# gat8_rev_1.net
KiCad netlist of a schematic drawn in EAGLE
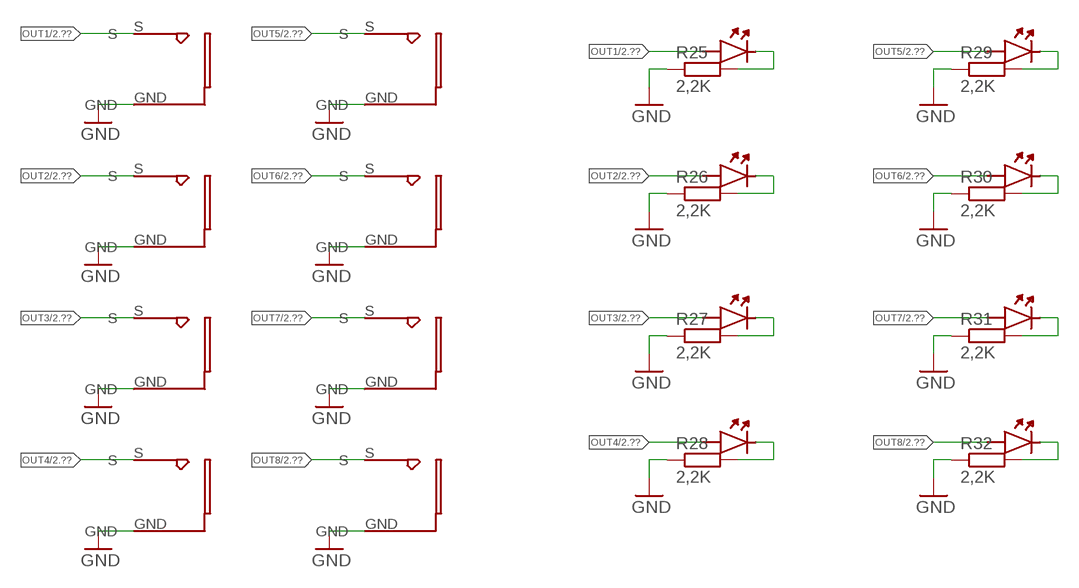
[diagram p0: schematic, sheet 1]
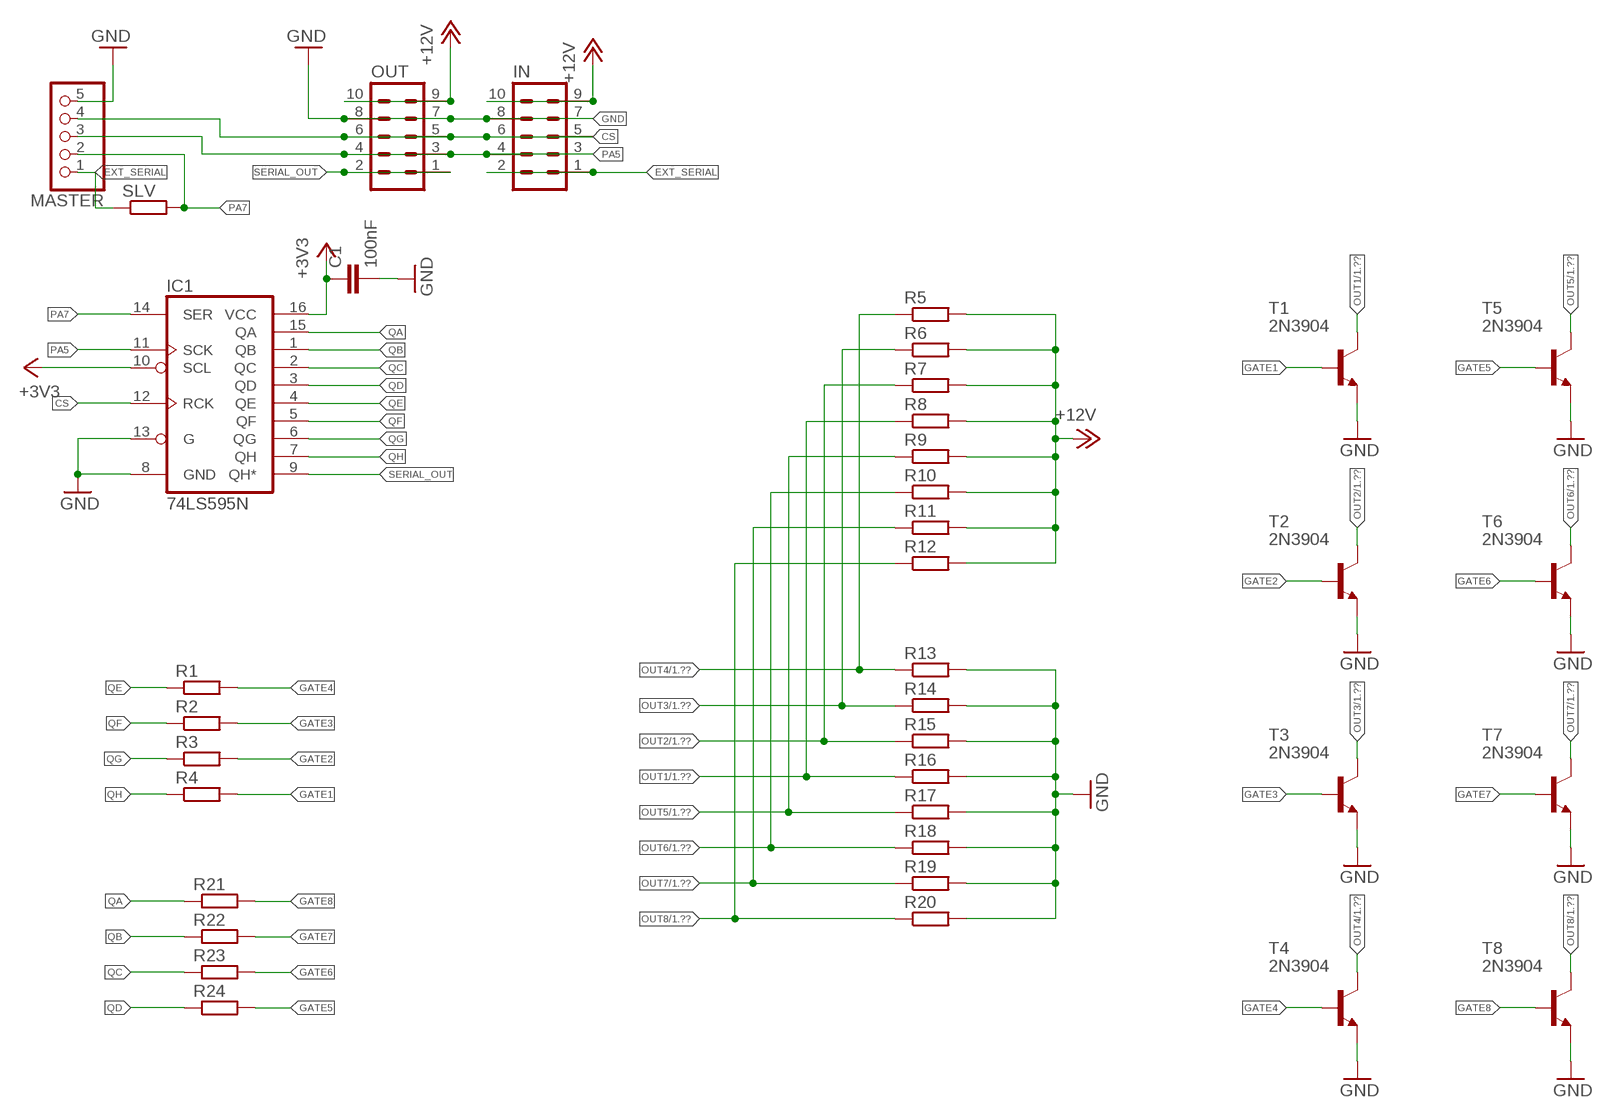
[diagram p1: schematic, sheet 2]
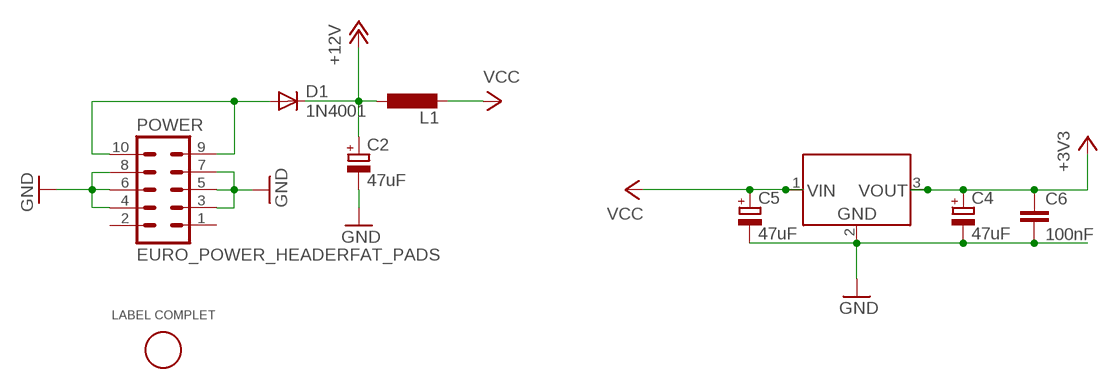
[diagram p2: schematic, sheet 3]

(export (version "E")
  (design (tool "Eeschema 10.0.6"))
  (components
    (comp (ref "C2")
      (value "47uF")
      (footprint "eagle-import:E2-5")
      (libsource (lib "eagle-import") (part "CPOL-EUE2-5"))
    )
    (comp (ref "C4")
      (value "47uF")
      (footprint "eagle-import:E2-5")
      (libsource (lib "eagle-import") (part "CPOL-EUE2-5"))
    )
    (comp (ref "C5")
      (value "47uF")
      (footprint "eagle-import:E2-5")
      (libsource (lib "eagle-import") (part "CPOL-EUE2-5"))
    )
    (comp (ref "C6")
      (value "100nF")
      (footprint "eagle-import:C1206K")
      (libsource (lib "eagle-import") (part "C-EUC1206K"))
    )
    (comp (ref "D1")
      (value "1N4001")
      (footprint "eagle-import:DO41-10")
      (libsource (lib "eagle-import") (part "1N4004"))
    )
    (comp (ref "IC2")
      (value "LM117-3.3V")
      (footprint "eagle-import:SOT223")
      (libsource (lib "eagle-import") (part "LM117-SOT223"))
    )
    (comp (ref "L1")
      (value "L-EU0207/10")
      (footprint "eagle-import:0207_10")
      (libsource (lib "eagle-import") (part "L-EU0207/10"))
    )
    (comp (ref "POWER")
      (value "EURO_POWER_HEADERFAT_PADS")
      (footprint "eagle-import:EURO_PWR_HEADER_FAT")
      (libsource (lib "eagle-import") (part "EURO_POWER_HEADERFAT_PADS"))
    )
    (comp (ref "U$9")
      (value "LABEL_COMPLETE")
      (footprint "eagle-import:LABELCOMPLETE")
      (libsource (lib "eagle-import") (part "LABEL_COMPLETE"))
    )
    (comp (ref "LED8")
      (value "LED")
      (footprint "eagle-import:LED")
      (libsource (lib "eagle-import") (part "LED"))
    )
    (comp (ref "OUT1")
      (value "PJ302M")
      (footprint "eagle-import:PJ302M")
      (libsource (lib "eagle-import") (part "PJ302M"))
    )
    (comp (ref "OUT2")
      (value "PJ302M")
      (footprint "eagle-import:PJ302M")
      (libsource (lib "eagle-import") (part "PJ302M"))
    )
    (comp (ref "OUT3")
      (value "PJ302M")
      (footprint "eagle-import:PJ302M")
      (libsource (lib "eagle-import") (part "PJ302M"))
    )
    (comp (ref "OUT4")
      (value "PJ302M")
      (footprint "eagle-import:PJ302M")
      (libsource (lib "eagle-import") (part "PJ302M"))
    )
    (comp (ref "OUT5")
      (value "PJ302M")
      (footprint "eagle-import:PJ302M")
      (libsource (lib "eagle-import") (part "PJ302M"))
    )
    (comp (ref "OUT6")
      (value "PJ302M")
      (footprint "eagle-import:PJ302M")
      (libsource (lib "eagle-import") (part "PJ302M"))
    )
    (comp (ref "OUT7")
      (value "PJ302M")
      (footprint "eagle-import:PJ302M")
      (libsource (lib "eagle-import") (part "PJ302M"))
    )
    (comp (ref "OUT8")
      (value "PJ302M")
      (footprint "eagle-import:PJ302M")
      (libsource (lib "eagle-import") (part "PJ302M"))
    )
    (comp (ref "R25")
      (value "2,2K")
      (footprint "eagle-import:R1206")
      (libsource (lib "eagle-import") (part "R-EU_R1206"))
    )
    (comp (ref "R26")
      (value "2,2K")
      (footprint "eagle-import:R1206")
      (libsource (lib "eagle-import") (part "R-EU_R1206"))
    )
    (comp (ref "R27")
      (value "2,2K")
      (footprint "eagle-import:R1206")
      (libsource (lib "eagle-import") (part "R-EU_R1206"))
    )
    (comp (ref "R28")
      (value "2,2K")
      (footprint "eagle-import:R1206")
      (libsource (lib "eagle-import") (part "R-EU_R1206"))
    )
    (comp (ref "R29")
      (value "2,2K")
      (footprint "eagle-import:R1206")
      (libsource (lib "eagle-import") (part "R-EU_R1206"))
    )
    (comp (ref "R30")
      (value "2,2K")
      (footprint "eagle-import:R1206")
      (libsource (lib "eagle-import") (part "R-EU_R1206"))
    )
    (comp (ref "R31")
      (value "2,2K")
      (footprint "eagle-import:R1206")
      (libsource (lib "eagle-import") (part "R-EU_R1206"))
    )
    (comp (ref "R32")
      (value "2,2K")
      (footprint "eagle-import:R1206")
      (libsource (lib "eagle-import") (part "R-EU_R1206"))
    )
    (comp (ref "U$1")
      (value "LED")
      (footprint "eagle-import:LED")
      (libsource (lib "eagle-import") (part "LED"))
    )
    (comp (ref "U$2")
      (value "LED")
      (footprint "eagle-import:LED")
      (libsource (lib "eagle-import") (part "LED"))
    )
    (comp (ref "U$3")
      (value "LED")
      (footprint "eagle-import:LED")
      (libsource (lib "eagle-import") (part "LED"))
    )
    (comp (ref "U$4")
      (value "LED")
      (footprint "eagle-import:LED")
      (libsource (lib "eagle-import") (part "LED"))
    )
    (comp (ref "U$5")
      (value "LED")
      (footprint "eagle-import:LED")
      (libsource (lib "eagle-import") (part "LED"))
    )
    (comp (ref "U$6")
      (value "LED")
      (footprint "eagle-import:LED")
      (libsource (lib "eagle-import") (part "LED"))
    )
    (comp (ref "U$7")
      (value "LED")
      (footprint "eagle-import:LED")
      (libsource (lib "eagle-import") (part "LED"))
    )
    (comp (ref "C1")
      (value "100nF")
      (footprint "eagle-import:C1206K")
      (libsource (lib "eagle-import") (part "C-EUC1206K"))
    )
    (comp (ref "IC1")
      (value "74LS595N")
      (footprint "eagle-import:DIL16")
      (libsource (lib "eagle-import") (part "74595NLS"))
    )
    (comp (ref "IN")
      (value "ML10")
      (footprint "eagle-import:ML10")
      (fields (field (name "OC_FARNELL") "unknown") (field (name "OC_NEWARK") "unknown"))
      (libsource (lib "eagle-import") (part "ML10"))
    )
    (comp (ref "MASTER")
      (value "PINHD-1X5_2.54")
      (footprint "eagle-import:1X05")
      (libsource (lib "eagle-import") (part "PINHD-1X5_2.54"))
    )
    (comp (ref "OUT")
      (value "ML10")
      (footprint "eagle-import:ML10")
      (libsource (lib "eagle-import") (part "ML10"))
    )
    (comp (ref "R1")
      (value "R-EU_R1206")
      (footprint "eagle-import:R1206")
      (libsource (lib "eagle-import") (part "R-EU_R1206"))
    )
    (comp (ref "R2")
      (value "R-EU_R1206")
      (footprint "eagle-import:R1206")
      (libsource (lib "eagle-import") (part "R-EU_R1206"))
    )
    (comp (ref "R3")
      (value "R-EU_R1206")
      (footprint "eagle-import:R1206")
      (libsource (lib "eagle-import") (part "R-EU_R1206"))
    )
    (comp (ref "R4")
      (value "R-EU_R1206")
      (footprint "eagle-import:R1206")
      (libsource (lib "eagle-import") (part "R-EU_R1206"))
    )
    (comp (ref "R5")
      (value "R-EU_R1206")
      (footprint "eagle-import:R1206")
      (libsource (lib "eagle-import") (part "R-EU_R1206"))
    )
    (comp (ref "R6")
      (value "R-EU_R1206")
      (footprint "eagle-import:R1206")
      (libsource (lib "eagle-import") (part "R-EU_R1206"))
    )
    (comp (ref "R7")
      (value "R-EU_R1206")
      (footprint "eagle-import:R1206")
      (libsource (lib "eagle-import") (part "R-EU_R1206"))
    )
    (comp (ref "R8")
      (value "R-EU_R1206")
      (footprint "eagle-import:R1206")
      (libsource (lib "eagle-import") (part "R-EU_R1206"))
    )
    (comp (ref "R9")
      (value "R-EU_R1206")
      (footprint "eagle-import:R1206")
      (libsource (lib "eagle-import") (part "R-EU_R1206"))
    )
    (comp (ref "R10")
      (value "R-EU_R1206")
      (footprint "eagle-import:R1206")
      (libsource (lib "eagle-import") (part "R-EU_R1206"))
    )
    (comp (ref "R11")
      (value "R-EU_R1206")
      (footprint "eagle-import:R1206")
      (libsource (lib "eagle-import") (part "R-EU_R1206"))
    )
    (comp (ref "R12")
      (value "R-EU_R1206")
      (footprint "eagle-import:R1206")
      (libsource (lib "eagle-import") (part "R-EU_R1206"))
    )
    (comp (ref "R13")
      (value "R-EU_R1206")
      (footprint "eagle-import:R1206")
      (libsource (lib "eagle-import") (part "R-EU_R1206"))
    )
    (comp (ref "R14")
      (value "R-EU_R1206")
      (footprint "eagle-import:R1206")
      (libsource (lib "eagle-import") (part "R-EU_R1206"))
    )
    (comp (ref "R15")
      (value "R-EU_R1206")
      (footprint "eagle-import:R1206")
      (libsource (lib "eagle-import") (part "R-EU_R1206"))
    )
    (comp (ref "R16")
      (value "R-EU_R1206")
      (footprint "eagle-import:R1206")
      (libsource (lib "eagle-import") (part "R-EU_R1206"))
    )
    (comp (ref "R17")
      (value "R-EU_R1206")
      (footprint "eagle-import:R1206")
      (libsource (lib "eagle-import") (part "R-EU_R1206"))
    )
    (comp (ref "R18")
      (value "R-EU_R1206")
      (footprint "eagle-import:R1206")
      (libsource (lib "eagle-import") (part "R-EU_R1206"))
    )
    (comp (ref "R19")
      (value "R-EU_R1206")
      (footprint "eagle-import:R1206")
      (libsource (lib "eagle-import") (part "R-EU_R1206"))
    )
    (comp (ref "R20")
      (value "R-EU_R1206")
      (footprint "eagle-import:R1206")
      (libsource (lib "eagle-import") (part "R-EU_R1206"))
    )
    (comp (ref "R21")
      (value "R-EU_R1206")
      (footprint "eagle-import:R1206")
      (libsource (lib "eagle-import") (part "R-EU_R1206"))
    )
    (comp (ref "R22")
      (value "R-EU_R1206")
      (footprint "eagle-import:R1206")
      (libsource (lib "eagle-import") (part "R-EU_R1206"))
    )
    (comp (ref "R23")
      (value "R-EU_R1206")
      (footprint "eagle-import:R1206")
      (libsource (lib "eagle-import") (part "R-EU_R1206"))
    )
    (comp (ref "R24")
      (value "R-EU_R1206")
      (footprint "eagle-import:R1206")
      (libsource (lib "eagle-import") (part "R-EU_R1206"))
    )
    (comp (ref "SLV")
      (value "R-EU_R0805")
      (footprint "eagle-import:R0805")
      (libsource (lib "eagle-import") (part "R-EU_R0805"))
    )
    (comp (ref "T1")
      (value "2N3904")
      (footprint "eagle-import:TO92")
      (libsource (lib "eagle-import") (part "2N3904"))
    )
    (comp (ref "T2")
      (value "2N3904")
      (footprint "eagle-import:TO92")
      (libsource (lib "eagle-import") (part "2N3904"))
    )
    (comp (ref "T3")
      (value "2N3904")
      (footprint "eagle-import:TO92")
      (libsource (lib "eagle-import") (part "2N3904"))
    )
    (comp (ref "T4")
      (value "2N3904")
      (footprint "eagle-import:TO92")
      (libsource (lib "eagle-import") (part "2N3904"))
    )
    (comp (ref "T5")
      (value "2N3904")
      (footprint "eagle-import:TO92")
      (libsource (lib "eagle-import") (part "2N3904"))
    )
    (comp (ref "T6")
      (value "2N3904")
      (footprint "eagle-import:TO92")
      (libsource (lib "eagle-import") (part "2N3904"))
    )
    (comp (ref "T7")
      (value "2N3904")
      (footprint "eagle-import:TO92")
      (libsource (lib "eagle-import") (part "2N3904"))
    )
    (comp (ref "T8")
      (value "2N3904")
      (footprint "eagle-import:TO92")
      (libsource (lib "eagle-import") (part "2N3904"))
    )
  )
  (nets
    (net (code "1") (name "+3V3") (class "Default")
      (node (ref "C1") (pin "1") (pinfunction "1_1") (pintype "passive"))
      (node (ref "C4") (pin "+") (pinfunction "+_+") (pintype "passive"))
      (node (ref "C6") (pin "1") (pinfunction "1_1") (pintype "passive"))
      (node (ref "IC1") (pin "10") (pinfunction "SCL_10") (pintype "input"))
      (node (ref "IC1") (pin "16") (pinfunction "VCC_16") (pintype "power_in"))
      (node (ref "IC2") (pin "3") (pinfunction "VOUT_3") (pintype "bidirectional"))
    )
    (net (code "2") (name "+12V") (class "Default")
      (node (ref "C2") (pin "+") (pinfunction "+_+") (pintype "passive"))
      (node (ref "D1") (pin "C") (pinfunction "C_C") (pintype "passive"))
      (node (ref "IN") (pin "10") (pinfunction "10_10") (pintype "passive"))
      (node (ref "IN") (pin "9") (pinfunction "9_9") (pintype "passive"))
      (node (ref "L1") (pin "1") (pinfunction "1_1") (pintype "passive"))
      (node (ref "OUT") (pin "10") (pinfunction "10_10") (pintype "passive"))
      (node (ref "OUT") (pin "9") (pinfunction "9_9") (pintype "passive"))
      (node (ref "R10") (pin "2") (pinfunction "2_2") (pintype "passive"))
      (node (ref "R11") (pin "2") (pinfunction "2_2") (pintype "passive"))
      (node (ref "R12") (pin "2") (pinfunction "2_2") (pintype "passive"))
      (node (ref "R5") (pin "2") (pinfunction "2_2") (pintype "passive"))
      (node (ref "R6") (pin "2") (pinfunction "2_2") (pintype "passive"))
      (node (ref "R7") (pin "2") (pinfunction "2_2") (pintype "passive"))
      (node (ref "R8") (pin "2") (pinfunction "2_2") (pintype "passive"))
      (node (ref "R9") (pin "2") (pinfunction "2_2") (pintype "passive"))
    )
    (net (code "3") (name "CS") (class "Default")
      (node (ref "IC1") (pin "12") (pinfunction "RCK_12") (pintype "input"))
      (node (ref "IN") (pin "5") (pinfunction "5_5") (pintype "passive"))
      (node (ref "IN") (pin "6") (pinfunction "6_6") (pintype "passive"))
      (node (ref "MASTER") (pin "4") (pinfunction "4_4") (pintype "passive"))
      (node (ref "OUT") (pin "5") (pinfunction "5_5") (pintype "passive"))
      (node (ref "OUT") (pin "6") (pinfunction "6_6") (pintype "passive"))
    )
    (net (code "4") (name "EXT_SERIAL") (class "Default")
      (node (ref "IN") (pin "1") (pinfunction "1_1") (pintype "passive"))
      (node (ref "IN") (pin "2") (pinfunction "2_2") (pintype "passive"))
      (node (ref "MASTER") (pin "1") (pinfunction "1_1") (pintype "passive"))
      (node (ref "SLV") (pin "1") (pinfunction "1_1") (pintype "passive"))
    )
    (net (code "5") (name "GATE1") (class "Default")
      (node (ref "R4") (pin "2") (pinfunction "2_2") (pintype "passive"))
      (node (ref "T1") (pin "2") (pinfunction "B_2") (pintype "passive"))
    )
    (net (code "6") (name "GATE2") (class "Default")
      (node (ref "R3") (pin "2") (pinfunction "2_2") (pintype "passive"))
      (node (ref "T2") (pin "2") (pinfunction "B_2") (pintype "passive"))
    )
    (net (code "7") (name "GATE3") (class "Default")
      (node (ref "R2") (pin "2") (pinfunction "2_2") (pintype "passive"))
      (node (ref "T3") (pin "2") (pinfunction "B_2") (pintype "passive"))
    )
    (net (code "8") (name "GATE4") (class "Default")
      (node (ref "R1") (pin "2") (pinfunction "2_2") (pintype "passive"))
      (node (ref "T4") (pin "2") (pinfunction "B_2") (pintype "passive"))
    )
    (net (code "9") (name "GATE5") (class "Default")
      (node (ref "R24") (pin "2") (pinfunction "2_2") (pintype "passive"))
      (node (ref "T5") (pin "2") (pinfunction "B_2") (pintype "passive"))
    )
    (net (code "10") (name "GATE6") (class "Default")
      (node (ref "R23") (pin "2") (pinfunction "2_2") (pintype "passive"))
      (node (ref "T6") (pin "2") (pinfunction "B_2") (pintype "passive"))
    )
    (net (code "11") (name "GATE7") (class "Default")
      (node (ref "R22") (pin "2") (pinfunction "2_2") (pintype "passive"))
      (node (ref "T7") (pin "2") (pinfunction "B_2") (pintype "passive"))
    )
    (net (code "12") (name "GATE8") (class "Default")
      (node (ref "R21") (pin "2") (pinfunction "2_2") (pintype "passive"))
      (node (ref "T8") (pin "2") (pinfunction "B_2") (pintype "passive"))
    )
    (net (code "13") (name "GND") (class "Default")
      (node (ref "C1") (pin "2") (pinfunction "2_2") (pintype "passive"))
      (node (ref "C2") (pin "-") (pinfunction "-_-") (pintype "passive"))
      (node (ref "C4") (pin "-") (pinfunction "-_-") (pintype "passive"))
      (node (ref "C5") (pin "-") (pinfunction "-_-") (pintype "passive"))
      (node (ref "C6") (pin "2") (pinfunction "2_2") (pintype "passive"))
      (node (ref "IC1") (pin "13") (pinfunction "G_13") (pintype "input"))
      (node (ref "IC1") (pin "8") (pinfunction "GND_8") (pintype "power_in"))
      (node (ref "IC2") (pin "2") (pinfunction "GND_2") (pintype "bidirectional"))
      (node (ref "IN") (pin "7") (pinfunction "7_7") (pintype "passive"))
      (node (ref "IN") (pin "8") (pinfunction "8_8") (pintype "passive"))
      (node (ref "MASTER") (pin "5") (pinfunction "5_5") (pintype "passive"))
      (node (ref "OUT") (pin "7") (pinfunction "7_7") (pintype "passive"))
      (node (ref "OUT") (pin "8") (pinfunction "8_8") (pintype "passive"))
      (node (ref "OUT1") (pin "GND") (pinfunction "GND_GND") (pintype "bidirectional"))
      (node (ref "OUT2") (pin "GND") (pinfunction "GND_GND") (pintype "bidirectional"))
      (node (ref "OUT3") (pin "GND") (pinfunction "GND_GND") (pintype "bidirectional"))
      (node (ref "OUT4") (pin "GND") (pinfunction "GND_GND") (pintype "bidirectional"))
      (node (ref "OUT5") (pin "GND") (pinfunction "GND_GND") (pintype "bidirectional"))
      (node (ref "OUT6") (pin "GND") (pinfunction "GND_GND") (pintype "bidirectional"))
      (node (ref "OUT7") (pin "GND") (pinfunction "GND_GND") (pintype "bidirectional"))
      (node (ref "OUT8") (pin "GND") (pinfunction "GND_GND") (pintype "bidirectional"))
      (node (ref "POWER") (pin "3") (pinfunction "3_3") (pintype "passive"))
      (node (ref "POWER") (pin "4") (pinfunction "4_4") (pintype "passive"))
      (node (ref "POWER") (pin "5") (pinfunction "5_5") (pintype "passive"))
      (node (ref "POWER") (pin "6") (pinfunction "6_6") (pintype "passive"))
      (node (ref "POWER") (pin "7") (pinfunction "7_7") (pintype "passive"))
      (node (ref "POWER") (pin "8") (pinfunction "8_8") (pintype "passive"))
      (node (ref "R13") (pin "2") (pinfunction "2_2") (pintype "passive"))
      (node (ref "R14") (pin "2") (pinfunction "2_2") (pintype "passive"))
      (node (ref "R15") (pin "2") (pinfunction "2_2") (pintype "passive"))
      (node (ref "R16") (pin "2") (pinfunction "2_2") (pintype "passive"))
      (node (ref "R17") (pin "2") (pinfunction "2_2") (pintype "passive"))
      (node (ref "R18") (pin "2") (pinfunction "2_2") (pintype "passive"))
      (node (ref "R19") (pin "2") (pinfunction "2_2") (pintype "passive"))
      (node (ref "R20") (pin "2") (pinfunction "2_2") (pintype "passive"))
      (node (ref "R25") (pin "1") (pinfunction "1_1") (pintype "passive"))
      (node (ref "R26") (pin "1") (pinfunction "1_1") (pintype "passive"))
      (node (ref "R27") (pin "1") (pinfunction "1_1") (pintype "passive"))
      (node (ref "R28") (pin "1") (pinfunction "1_1") (pintype "passive"))
      (node (ref "R29") (pin "1") (pinfunction "1_1") (pintype "passive"))
      (node (ref "R30") (pin "1") (pinfunction "1_1") (pintype "passive"))
      (node (ref "R31") (pin "1") (pinfunction "1_1") (pintype "passive"))
      (node (ref "R32") (pin "1") (pinfunction "1_1") (pintype "passive"))
      (node (ref "T1") (pin "3") (pinfunction "E_3") (pintype "passive"))
      (node (ref "T2") (pin "3") (pinfunction "E_3") (pintype "passive"))
      (node (ref "T3") (pin "3") (pinfunction "E_3") (pintype "passive"))
      (node (ref "T4") (pin "3") (pinfunction "E_3") (pintype "passive"))
      (node (ref "T5") (pin "3") (pinfunction "E_3") (pintype "passive"))
      (node (ref "T6") (pin "3") (pinfunction "E_3") (pintype "passive"))
      (node (ref "T7") (pin "3") (pinfunction "E_3") (pintype "passive"))
      (node (ref "T8") (pin "3") (pinfunction "E_3") (pintype "passive"))
    )
    (net (code "14") (name "Net-(D1-PadA)") (class "Default")
      (node (ref "D1") (pin "A") (pinfunction "A_A") (pintype "passive"))
      (node (ref "POWER") (pin "10") (pinfunction "10_10") (pintype "passive"))
      (node (ref "POWER") (pin "9") (pinfunction "9_9") (pintype "passive"))
    )
    (net (code "15") (name "Net-(LED8-PadGND)") (class "Default")
      (node (ref "LED8") (pin "GND") (pinfunction "GND_GND") (pintype "output"))
      (node (ref "R32") (pin "2") (pinfunction "2_2") (pintype "passive"))
    )
    (net (code "16") (name "Net-(R25-Pad2)") (class "Default")
      (node (ref "R25") (pin "2") (pinfunction "2_2") (pintype "passive"))
      (node (ref "U$1") (pin "GND") (pinfunction "GND_GND") (pintype "output"))
    )
    (net (code "17") (name "Net-(R26-Pad2)") (class "Default")
      (node (ref "R26") (pin "2") (pinfunction "2_2") (pintype "passive"))
      (node (ref "U$2") (pin "GND") (pinfunction "GND_GND") (pintype "output"))
    )
    (net (code "18") (name "Net-(R27-Pad2)") (class "Default")
      (node (ref "R27") (pin "2") (pinfunction "2_2") (pintype "passive"))
      (node (ref "U$3") (pin "GND") (pinfunction "GND_GND") (pintype "output"))
    )
    (net (code "19") (name "Net-(R28-Pad2)") (class "Default")
      (node (ref "R28") (pin "2") (pinfunction "2_2") (pintype "passive"))
      (node (ref "U$4") (pin "GND") (pinfunction "GND_GND") (pintype "output"))
    )
    (net (code "20") (name "Net-(R29-Pad2)") (class "Default")
      (node (ref "R29") (pin "2") (pinfunction "2_2") (pintype "passive"))
      (node (ref "U$5") (pin "GND") (pinfunction "GND_GND") (pintype "output"))
    )
    (net (code "21") (name "Net-(R30-Pad2)") (class "Default")
      (node (ref "R30") (pin "2") (pinfunction "2_2") (pintype "passive"))
      (node (ref "U$6") (pin "GND") (pinfunction "GND_GND") (pintype "output"))
    )
    (net (code "22") (name "Net-(R31-Pad2)") (class "Default")
      (node (ref "R31") (pin "2") (pinfunction "2_2") (pintype "passive"))
      (node (ref "U$7") (pin "GND") (pinfunction "GND_GND") (pintype "output"))
    )
    (net (code "23") (name "OUT1") (class "Default")
      (node (ref "OUT1") (pin "S") (pinfunction "S_S") (pintype "bidirectional"))
      (node (ref "R16") (pin "1") (pinfunction "1_1") (pintype "passive"))
      (node (ref "R8") (pin "1") (pinfunction "1_1") (pintype "passive"))
      (node (ref "T1") (pin "1") (pinfunction "C_1") (pintype "passive"))
      (node (ref "U$1") (pin "S") (pinfunction "S_S") (pintype "input"))
    )
    (net (code "24") (name "OUT2") (class "Default")
      (node (ref "OUT2") (pin "S") (pinfunction "S_S") (pintype "bidirectional"))
      (node (ref "R15") (pin "1") (pinfunction "1_1") (pintype "passive"))
      (node (ref "R7") (pin "1") (pinfunction "1_1") (pintype "passive"))
      (node (ref "T2") (pin "1") (pinfunction "C_1") (pintype "passive"))
      (node (ref "U$2") (pin "S") (pinfunction "S_S") (pintype "input"))
    )
    (net (code "25") (name "OUT3") (class "Default")
      (node (ref "OUT3") (pin "S") (pinfunction "S_S") (pintype "bidirectional"))
      (node (ref "R14") (pin "1") (pinfunction "1_1") (pintype "passive"))
      (node (ref "R6") (pin "1") (pinfunction "1_1") (pintype "passive"))
      (node (ref "T3") (pin "1") (pinfunction "C_1") (pintype "passive"))
      (node (ref "U$3") (pin "S") (pinfunction "S_S") (pintype "input"))
    )
    (net (code "26") (name "OUT4") (class "Default")
      (node (ref "OUT4") (pin "S") (pinfunction "S_S") (pintype "bidirectional"))
      (node (ref "R13") (pin "1") (pinfunction "1_1") (pintype "passive"))
      (node (ref "R5") (pin "1") (pinfunction "1_1") (pintype "passive"))
      (node (ref "T4") (pin "1") (pinfunction "C_1") (pintype "passive"))
      (node (ref "U$4") (pin "S") (pinfunction "S_S") (pintype "input"))
    )
    (net (code "27") (name "OUT5") (class "Default")
      (node (ref "OUT5") (pin "S") (pinfunction "S_S") (pintype "bidirectional"))
      (node (ref "R17") (pin "1") (pinfunction "1_1") (pintype "passive"))
      (node (ref "R9") (pin "1") (pinfunction "1_1") (pintype "passive"))
      (node (ref "T5") (pin "1") (pinfunction "C_1") (pintype "passive"))
      (node (ref "U$5") (pin "S") (pinfunction "S_S") (pintype "input"))
    )
    (net (code "28") (name "OUT6") (class "Default")
      (node (ref "OUT6") (pin "S") (pinfunction "S_S") (pintype "bidirectional"))
      (node (ref "R10") (pin "1") (pinfunction "1_1") (pintype "passive"))
      (node (ref "R18") (pin "1") (pinfunction "1_1") (pintype "passive"))
      (node (ref "T6") (pin "1") (pinfunction "C_1") (pintype "passive"))
      (node (ref "U$6") (pin "S") (pinfunction "S_S") (pintype "input"))
    )
    (net (code "29") (name "OUT7") (class "Default")
      (node (ref "OUT7") (pin "S") (pinfunction "S_S") (pintype "bidirectional"))
      (node (ref "R11") (pin "1") (pinfunction "1_1") (pintype "passive"))
      (node (ref "R19") (pin "1") (pinfunction "1_1") (pintype "passive"))
      (node (ref "T7") (pin "1") (pinfunction "C_1") (pintype "passive"))
      (node (ref "U$7") (pin "S") (pinfunction "S_S") (pintype "input"))
    )
    (net (code "30") (name "OUT8") (class "Default")
      (node (ref "LED8") (pin "S") (pinfunction "S_S") (pintype "input"))
      (node (ref "OUT8") (pin "S") (pinfunction "S_S") (pintype "bidirectional"))
      (node (ref "R12") (pin "1") (pinfunction "1_1") (pintype "passive"))
      (node (ref "R20") (pin "1") (pinfunction "1_1") (pintype "passive"))
      (node (ref "T8") (pin "1") (pinfunction "C_1") (pintype "passive"))
    )
    (net (code "31") (name "PA5") (class "Default")
      (node (ref "IC1") (pin "11") (pinfunction "SCK_11") (pintype "input"))
      (node (ref "IN") (pin "3") (pinfunction "3_3") (pintype "passive"))
      (node (ref "IN") (pin "4") (pinfunction "4_4") (pintype "passive"))
      (node (ref "MASTER") (pin "3") (pinfunction "3_3") (pintype "passive"))
      (node (ref "OUT") (pin "3") (pinfunction "3_3") (pintype "passive"))
      (node (ref "OUT") (pin "4") (pinfunction "4_4") (pintype "passive"))
    )
    (net (code "32") (name "PA7") (class "Default")
      (node (ref "IC1") (pin "14") (pinfunction "SER_14") (pintype "input"))
      (node (ref "MASTER") (pin "2") (pinfunction "2_2") (pintype "passive"))
      (node (ref "SLV") (pin "2") (pinfunction "2_2") (pintype "passive"))
    )
    (net (code "33") (name "QA") (class "Default")
      (node (ref "IC1") (pin "15") (pinfunction "QA_15") (pintype "tri_state"))
      (node (ref "R21") (pin "1") (pinfunction "1_1") (pintype "passive"))
    )
    (net (code "34") (name "QB") (class "Default")
      (node (ref "IC1") (pin "1") (pinfunction "QB_1") (pintype "tri_state"))
      (node (ref "R22") (pin "1") (pinfunction "1_1") (pintype "passive"))
    )
    (net (code "35") (name "QC") (class "Default")
      (node (ref "IC1") (pin "2") (pinfunction "QC_2") (pintype "tri_state"))
      (node (ref "R23") (pin "1") (pinfunction "1_1") (pintype "passive"))
    )
    (net (code "36") (name "QD") (class "Default")
      (node (ref "IC1") (pin "3") (pinfunction "QD_3") (pintype "tri_state"))
      (node (ref "R24") (pin "1") (pinfunction "1_1") (pintype "passive"))
    )
    (net (code "37") (name "QE") (class "Default")
      (node (ref "IC1") (pin "4") (pinfunction "QE_4") (pintype "tri_state"))
      (node (ref "R1") (pin "1") (pinfunction "1_1") (pintype "passive"))
    )
    (net (code "38") (name "QF") (class "Default")
      (node (ref "IC1") (pin "5") (pinfunction "QF_5") (pintype "tri_state"))
      (node (ref "R2") (pin "1") (pinfunction "1_1") (pintype "passive"))
    )
    (net (code "39") (name "QG") (class "Default")
      (node (ref "IC1") (pin "6") (pinfunction "QG_6") (pintype "tri_state"))
      (node (ref "R3") (pin "1") (pinfunction "1_1") (pintype "passive"))
    )
    (net (code "40") (name "QH") (class "Default")
      (node (ref "IC1") (pin "7") (pinfunction "QH_7") (pintype "tri_state"))
      (node (ref "R4") (pin "1") (pinfunction "1_1") (pintype "passive"))
    )
    (net (code "41") (name "SERIAL_OUT") (class "Default")
      (node (ref "IC1") (pin "9") (pinfunction "QH*_9") (pintype "tri_state"))
      (node (ref "OUT") (pin "1") (pinfunction "1_1") (pintype "passive"))
      (node (ref "OUT") (pin "2") (pinfunction "2_2") (pintype "passive"))
    )
    (net (code "42") (name "VCC") (class "Default")
      (node (ref "C5") (pin "+") (pinfunction "+_+") (pintype "passive"))
      (node (ref "IC2") (pin "1") (pinfunction "VIN_1") (pintype "bidirectional"))
      (node (ref "L1") (pin "2") (pinfunction "2_2") (pintype "passive"))
    )
    (net (code "43") (name "unconnected-(POWER-Pad1)") (class "Default")
      (node (ref "POWER") (pin "1") (pinfunction "1_1") (pintype "passive"))
    )
    (net (code "44") (name "unconnected-(POWER-Pad2)") (class "Default")
      (node (ref "POWER") (pin "2") (pinfunction "2_2") (pintype "passive"))
    )
  )
)
